# Power.net
KiCad netlist of a schematic drawn in EAGLE
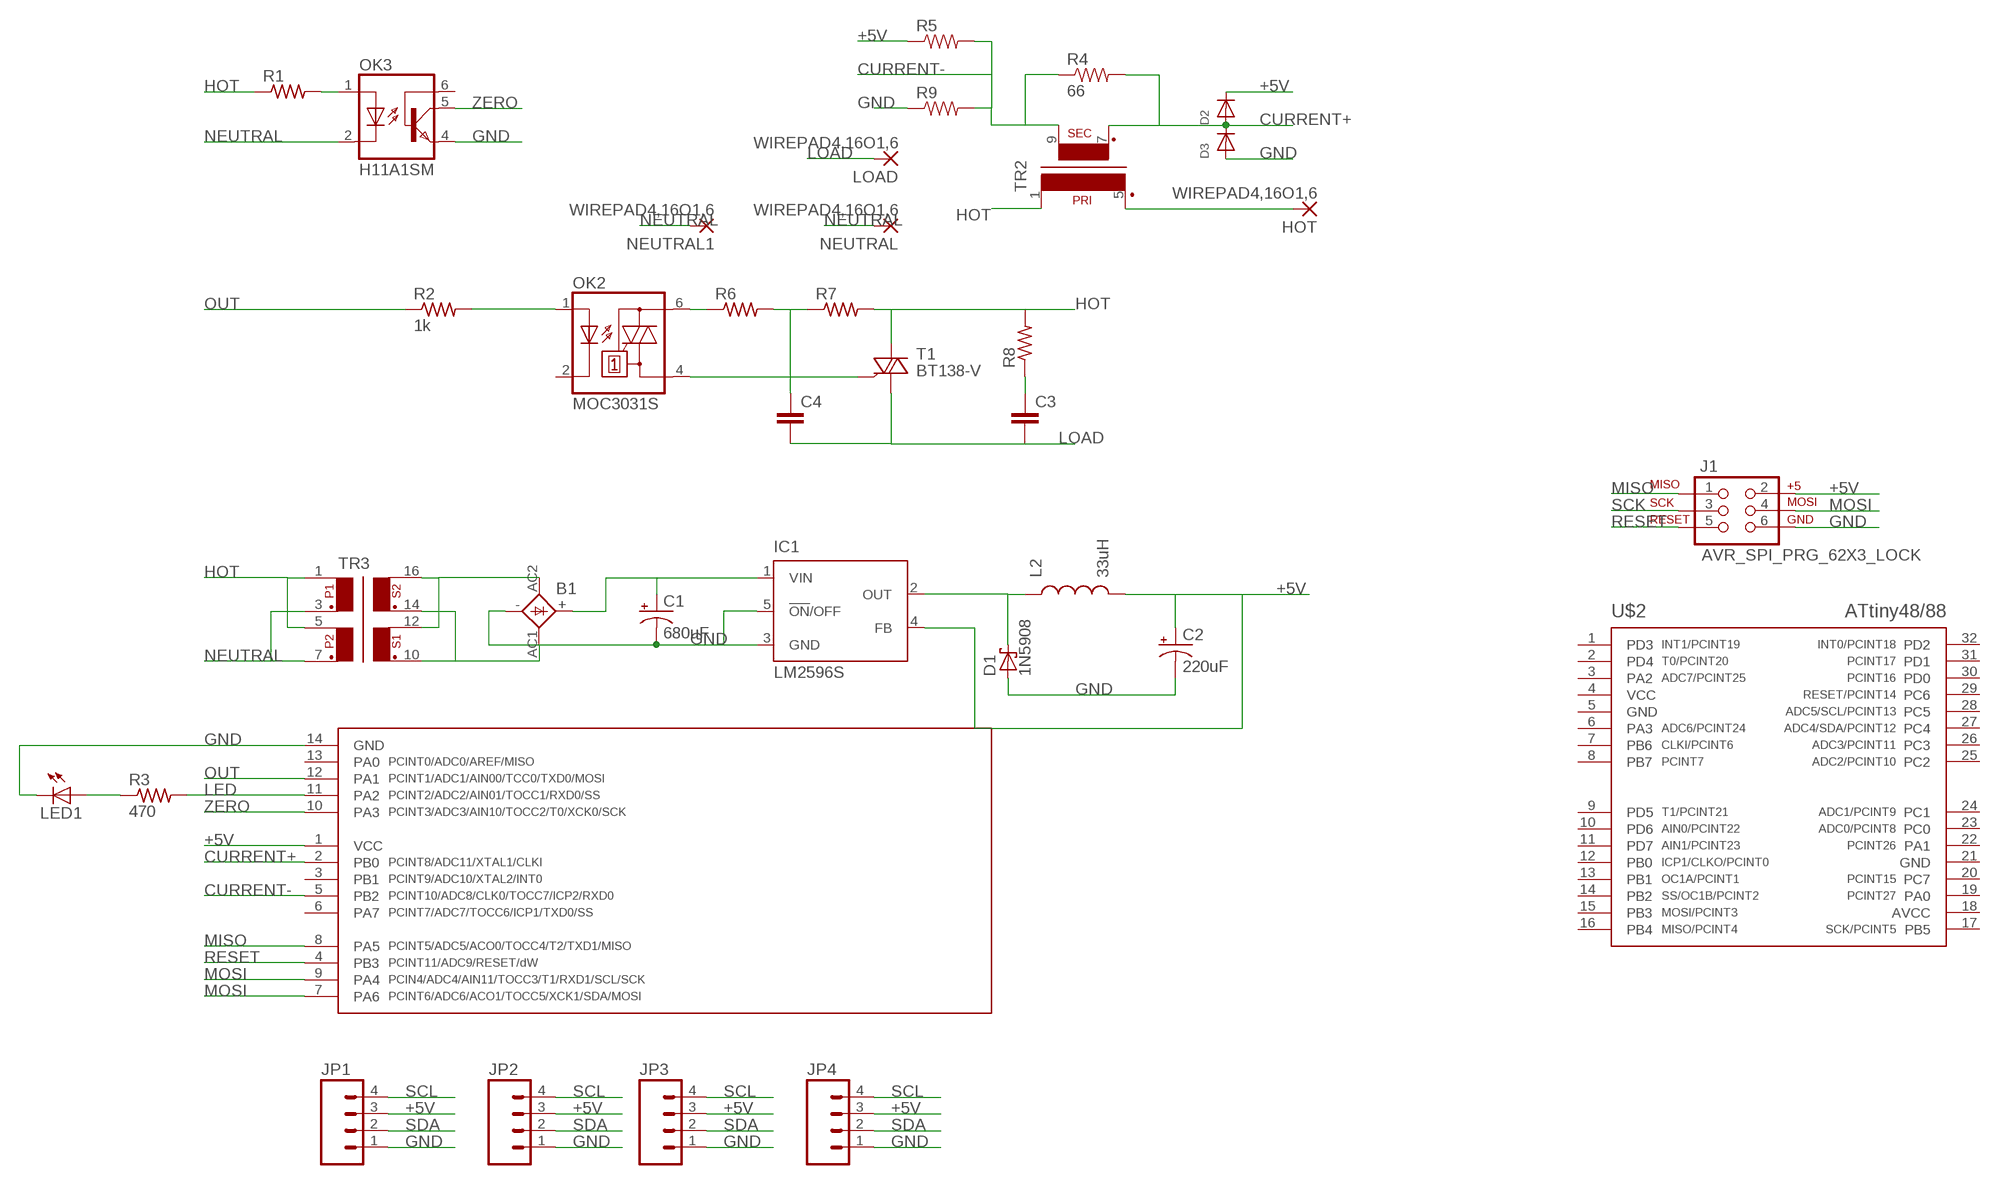
[diagram p0: schematic, sheet 1]

(export (version "E")
  (design (tool "Eeschema 10.0.6"))
  (components
    (comp (ref "B1")
      (value "GBU4")
      (footprint "eagle-import:GBU4S")
      (libsource (lib "eagle-import") (part "GBU4"))
    )
    (comp (ref "C1")
      (value "680uF")
      (footprint "eagle-import:PANASONIC_H13")
      (libsource (lib "eagle-import") (part "CAP_POLH13"))
    )
    (comp (ref "C2")
      (value "220uF")
      (footprint "eagle-import:PANASONIC_D")
      (libsource (lib "eagle-import") (part "CAP_POLD"))
    )
    (comp (ref "C3")
      (value "C-EUC1206")
      (footprint "eagle-import:C1206")
      (libsource (lib "eagle-import") (part "C-EUC1206"))
    )
    (comp (ref "C4")
      (value "C-EUC1206")
      (footprint "eagle-import:C1206")
      (libsource (lib "eagle-import") (part "C-EUC1206"))
    )
    (comp (ref "D1")
      (value "1N5908")
      (footprint "eagle-import:C4111-15")
      (libsource (lib "eagle-import") (part "1N5908"))
    )
    (comp (ref "D2")
      (value "DIODESMA")
      (footprint "eagle-import:SMADIODE")
      (libsource (lib "eagle-import") (part "DIODESMA"))
    )
    (comp (ref "D3")
      (value "DIODESMA")
      (footprint "eagle-import:SMADIODE")
      (libsource (lib "eagle-import") (part "DIODESMA"))
    )
    (comp (ref "HOT")
      (value "WIREPAD4,16O1,6")
      (footprint "eagle-import:4,16O1,6")
      (libsource (lib "eagle-import") (part "WIREPAD4,16O1,6"))
    )
    (comp (ref "IC1")
      (value "LM2596S")
      (footprint "eagle-import:TO263-5")
      (fields (field (name "MF") "NATIONAL SEMICONDUCTOR") (field (name "MPN") "LM2596S-ADJ/NOPB"))
      (libsource (lib "eagle-import") (part "LM2596S"))
    )
    (comp (ref "J1")
      (value "AVR_SPI_PRG_62X3_LOCK")
      (footprint "eagle-import:2X3_LOCK")
      (libsource (lib "eagle-import") (part "AVR_SPI_PRG_62X3_LOCK"))
    )
    (comp (ref "JP1")
      (value "M04JST-PTH")
      (footprint "eagle-import:JST-4-PTH")
      (libsource (lib "eagle-import") (part "M04JST-PTH"))
    )
    (comp (ref "JP2")
      (value "M04JST-PTH")
      (footprint "eagle-import:JST-4-PTH")
      (libsource (lib "eagle-import") (part "M04JST-PTH"))
    )
    (comp (ref "JP3")
      (value "M04JST-PTH")
      (footprint "eagle-import:JST-4-PTH")
      (libsource (lib "eagle-import") (part "M04JST-PTH"))
    )
    (comp (ref "JP4")
      (value "M04JST-PTH")
      (footprint "eagle-import:JST-4-PTH")
      (libsource (lib "eagle-import") (part "M04JST-PTH"))
    )
    (comp (ref "L2")
      (value "33uH")
      (footprint "eagle-import:SRN6045")
      (libsource (lib "eagle-import") (part "INDUCTORBOURNS_SRN6045"))
    )
    (comp (ref "LED1")
      (value "LED1206")
      (footprint "eagle-import:LED-1206")
      (libsource (lib "eagle-import") (part "LED1206"))
    )
    (comp (ref "LOAD")
      (value "WIREPAD4,16O1,6")
      (footprint "eagle-import:4,16O1,6")
      (libsource (lib "eagle-import") (part "WIREPAD4,16O1,6"))
    )
    (comp (ref "NEUTRAL")
      (value "WIREPAD4,16O1,6")
      (footprint "eagle-import:4,16O1,6")
      (libsource (lib "eagle-import") (part "WIREPAD4,16O1,6"))
    )
    (comp (ref "NEUTRAL1")
      (value "WIREPAD4,16O1,6")
      (footprint "eagle-import:4,16O1,6")
      (libsource (lib "eagle-import") (part "WIREPAD4,16O1,6"))
    )
    (comp (ref "OK2")
      (value "MOC3031S")
      (footprint "eagle-import:DIL6-SMD")
      (fields (field (name "MF") "FAIRCHILD SEMICONDUCTOR") (field (name "MPN") "MOC3031SM"))
      (libsource (lib "eagle-import") (part "MOC30S31"))
    )
    (comp (ref "OK3")
      (value "H11A1SM")
      (footprint "eagle-import:DIL6-SMD")
      (libsource (lib "eagle-import") (part "H11A?MS1"))
    )
    (comp (ref "R1")
      (value "R-US_R1206")
      (footprint "eagle-import:R1206")
      (libsource (lib "eagle-import") (part "R-US_R1206"))
    )
    (comp (ref "R2")
      (value "1k")
      (footprint "eagle-import:R1206")
      (libsource (lib "eagle-import") (part "R-US_R1206"))
    )
    (comp (ref "R3")
      (value "470")
      (footprint "eagle-import:R1206")
      (libsource (lib "eagle-import") (part "R-US_R1206"))
    )
    (comp (ref "R4")
      (value "66")
      (footprint "eagle-import:1206")
      (libsource (lib "eagle-import") (part "RESISTOR1206"))
    )
    (comp (ref "R5")
      (value "RESISTOR1206")
      (footprint "eagle-import:1206")
      (libsource (lib "eagle-import") (part "RESISTOR1206"))
    )
    (comp (ref "R6")
      (value "R-US_R1206")
      (footprint "eagle-import:R1206")
      (libsource (lib "eagle-import") (part "R-US_R1206"))
    )
    (comp (ref "R7")
      (value "R-US_R1206")
      (footprint "eagle-import:R1206")
      (libsource (lib "eagle-import") (part "R-US_R1206"))
    )
    (comp (ref "R8")
      (value "R-US_R1206")
      (footprint "eagle-import:R1206")
      (libsource (lib "eagle-import") (part "R-US_R1206"))
    )
    (comp (ref "R9")
      (value "RESISTOR1206")
      (footprint "eagle-import:1206")
      (libsource (lib "eagle-import") (part "RESISTOR1206"))
    )
    (comp (ref "T1")
      (value "BT138-V")
      (footprint "eagle-import:TO220BV")
      (libsource (lib "eagle-import") (part "BT138-V"))
    )
    (comp (ref "TR2")
      (value "VV11")
      (footprint "eagle-import:VV11")
      (libsource (lib "eagle-import") (part "VV11"))
    )
    (comp (ref "TR3")
      (value "FT04-10")
      (footprint "eagle-import:FT04-10")
      (libsource (lib "eagle-import") (part "FT04-10"))
    )
    (comp (ref "U$1")
      (value "TINY841")
      (footprint "eagle-import:SOIC14")
      (libsource (lib "eagle-import") (part "TINY841"))
    )
    (comp (ref "U$2")
      (value "ATTINY48/88-TQFP")
      (footprint "eagle-import:TQFP-32")
      (libsource (lib "eagle-import") (part "ATTINY48/88-TQFP"))
    )
  )
  (nets
    (net (code "1") (name "/+5V") (class "Default")
      (node (ref "C2") (pin "+") (pinfunction "+_+") (pintype "passive"))
      (node (ref "D2") (pin "C") (pinfunction "C_C") (pintype "passive"))
      (node (ref "IC1") (pin "4") (pinfunction "FB_4") (pintype "input"))
      (node (ref "J1") (pin "2") (pinfunction "2_2") (pintype "passive"))
      (node (ref "JP1") (pin "3") (pinfunction "3_3") (pintype "passive"))
      (node (ref "JP2") (pin "3") (pinfunction "3_3") (pintype "passive"))
      (node (ref "JP3") (pin "3") (pinfunction "3_3") (pintype "passive"))
      (node (ref "JP4") (pin "3") (pinfunction "3_3") (pintype "passive"))
      (node (ref "L2") (pin "2") (pinfunction "2_2") (pintype "passive"))
      (node (ref "R5") (pin "1") (pinfunction "1_1") (pintype "passive"))
      (node (ref "U$1") (pin "1") (pinfunction "VCC_1") (pintype "bidirectional"))
    )
    (net (code "2") (name "/AVCC") (class "Default")
      (node (ref "U$2") (pin "18") (pinfunction "AVCC_18") (pintype "power_in"))
    )
    (net (code "3") (name "/CURRENT+") (class "Default")
      (node (ref "D2") (pin "A") (pinfunction "A_A") (pintype "passive"))
      (node (ref "D3") (pin "C") (pinfunction "C_C") (pintype "passive"))
      (node (ref "R4") (pin "2") (pinfunction "2_2") (pintype "passive"))
      (node (ref "TR2") (pin "7") (pinfunction "S3_7") (pintype "passive"))
      (node (ref "U$1") (pin "2") (pinfunction "PB0_2") (pintype "bidirectional"))
    )
    (net (code "4") (name "/CURRENT-") (class "Default")
      (node (ref "R4") (pin "1") (pinfunction "1_1") (pintype "passive"))
      (node (ref "R5") (pin "2") (pinfunction "2_2") (pintype "passive"))
      (node (ref "R9") (pin "2") (pinfunction "2_2") (pintype "passive"))
      (node (ref "TR2") (pin "9") (pinfunction "S4_9") (pintype "passive"))
      (node (ref "U$1") (pin "5") (pinfunction "PB2_5") (pintype "bidirectional"))
    )
    (net (code "5") (name "/GND") (class "Default")
      (node (ref "B1") (pin "-") (pinfunction "-_-") (pintype "passive"))
      (node (ref "C1") (pin "-") (pinfunction "-_-") (pintype "passive"))
      (node (ref "C2") (pin "-") (pinfunction "-_-") (pintype "passive"))
      (node (ref "D1") (pin "A") (pinfunction "A_A") (pintype "passive"))
      (node (ref "D3") (pin "A") (pinfunction "A_A") (pintype "passive"))
      (node (ref "IC1") (pin "3") (pinfunction "GND_3") (pintype "power_in"))
      (node (ref "IC1") (pin "5") (pinfunction "~{ON}/OFF_5") (pintype "input"))
      (node (ref "J1") (pin "6") (pinfunction "6_6") (pintype "passive"))
      (node (ref "JP1") (pin "1") (pinfunction "1_1") (pintype "passive"))
      (node (ref "JP2") (pin "1") (pinfunction "1_1") (pintype "passive"))
      (node (ref "JP3") (pin "1") (pinfunction "1_1") (pintype "passive"))
      (node (ref "JP4") (pin "1") (pinfunction "1_1") (pintype "passive"))
      (node (ref "LED1") (pin "C") (pinfunction "C_C") (pintype "passive"))
      (node (ref "OK3") (pin "4") (pinfunction "EMI_4") (pintype "passive"))
      (node (ref "R9") (pin "1") (pinfunction "1_1") (pintype "passive"))
      (node (ref "U$1") (pin "14") (pinfunction "GND_14") (pintype "bidirectional"))
    )
    (net (code "6") (name "/HOT") (class "Default")
      (node (ref "R1") (pin "1") (pinfunction "1_1") (pintype "passive"))
      (node (ref "R7") (pin "2") (pinfunction "2_2") (pintype "passive"))
      (node (ref "R8") (pin "2") (pinfunction "2_2") (pintype "passive"))
      (node (ref "T1") (pin "T2") (pinfunction "A2_T2") (pintype "passive"))
      (node (ref "TR2") (pin "1") (pinfunction "P1_1") (pintype "passive"))
      (node (ref "TR3") (pin "1") (pinfunction "1_1") (pintype "passive"))
      (node (ref "TR3") (pin "5") (pinfunction "3_5") (pintype "passive"))
    )
    (net (code "7") (name "/LED") (class "Default")
      (node (ref "R3") (pin "2") (pinfunction "2_2") (pintype "passive"))
      (node (ref "U$1") (pin "11") (pinfunction "PA2_11") (pintype "bidirectional"))
    )
    (net (code "8") (name "/LOAD") (class "Default")
      (node (ref "C3") (pin "2") (pinfunction "2_2") (pintype "passive"))
      (node (ref "C4") (pin "2") (pinfunction "2_2") (pintype "passive"))
      (node (ref "LOAD") (pin "1") (pinfunction "P_1") (pintype "passive"))
      (node (ref "T1") (pin "T1") (pinfunction "A1_T1") (pintype "passive"))
    )
    (net (code "9") (name "/MISO") (class "Default")
      (node (ref "J1") (pin "1") (pinfunction "1_1") (pintype "passive"))
      (node (ref "U$1") (pin "8") (pinfunction "PA5_8") (pintype "bidirectional"))
    )
    (net (code "10") (name "/MOSI") (class "Default")
      (node (ref "J1") (pin "4") (pinfunction "4_4") (pintype "passive"))
      (node (ref "U$1") (pin "7") (pinfunction "PA6_7") (pintype "bidirectional"))
      (node (ref "U$1") (pin "9") (pinfunction "PA4_9") (pintype "bidirectional"))
    )
    (net (code "11") (name "/NEUTRAL") (class "Default")
      (node (ref "NEUTRAL") (pin "1") (pinfunction "P_1") (pintype "passive"))
      (node (ref "NEUTRAL1") (pin "1") (pinfunction "P_1") (pintype "passive"))
      (node (ref "OK3") (pin "2") (pinfunction "C_2") (pintype "passive"))
      (node (ref "TR3") (pin "3") (pinfunction "2_3") (pintype "passive"))
      (node (ref "TR3") (pin "7") (pinfunction "4_7") (pintype "passive"))
    )
    (net (code "12") (name "/OUT") (class "Default")
      (node (ref "R2") (pin "1") (pinfunction "1_1") (pintype "passive"))
      (node (ref "U$1") (pin "12") (pinfunction "PA1_12") (pintype "bidirectional"))
    )
    (net (code "13") (name "/RESET") (class "Default")
      (node (ref "J1") (pin "5") (pinfunction "5_5") (pintype "passive"))
      (node (ref "U$1") (pin "4") (pinfunction "PB3_4") (pintype "bidirectional"))
    )
    (net (code "14") (name "/SCK") (class "Default")
      (node (ref "J1") (pin "3") (pinfunction "3_3") (pintype "passive"))
    )
    (net (code "15") (name "/SCL") (class "Default")
      (node (ref "JP1") (pin "4") (pinfunction "4_4") (pintype "passive"))
      (node (ref "JP2") (pin "4") (pinfunction "4_4") (pintype "passive"))
      (node (ref "JP3") (pin "4") (pinfunction "4_4") (pintype "passive"))
      (node (ref "JP4") (pin "4") (pinfunction "4_4") (pintype "passive"))
    )
    (net (code "16") (name "/SDA") (class "Default")
      (node (ref "JP1") (pin "2") (pinfunction "2_2") (pintype "passive"))
      (node (ref "JP2") (pin "2") (pinfunction "2_2") (pintype "passive"))
      (node (ref "JP3") (pin "2") (pinfunction "2_2") (pintype "passive"))
      (node (ref "JP4") (pin "2") (pinfunction "2_2") (pintype "passive"))
    )
    (net (code "17") (name "/ZERO") (class "Default")
      (node (ref "OK3") (pin "5") (pinfunction "COL_5") (pintype "passive"))
      (node (ref "U$1") (pin "10") (pinfunction "PA3_10") (pintype "bidirectional"))
    )
    (net (code "18") (name "Net-(B1-AC1)") (class "Default")
      (node (ref "B1") (pin "AC2") (pinfunction "AC1_AC2") (pintype "passive"))
      (node (ref "TR3") (pin "12") (pinfunction "6_12") (pintype "passive"))
      (node (ref "TR3") (pin "16") (pinfunction "8_16") (pintype "passive"))
    )
    (net (code "19") (name "Net-(B1-AC2)") (class "Default")
      (node (ref "B1") (pin "AC1") (pinfunction "AC2_AC1") (pintype "passive"))
      (node (ref "TR3") (pin "10") (pinfunction "5_10") (pintype "passive"))
      (node (ref "TR3") (pin "14") (pinfunction "7_14") (pintype "passive"))
    )
    (net (code "20") (name "Net-(C3-Pad1)") (class "Default")
      (node (ref "C3") (pin "1") (pinfunction "1_1") (pintype "passive"))
      (node (ref "R8") (pin "1") (pinfunction "1_1") (pintype "passive"))
    )
    (net (code "21") (name "Net-(C4-Pad1)") (class "Default")
      (node (ref "C4") (pin "1") (pinfunction "1_1") (pintype "passive"))
      (node (ref "R6") (pin "2") (pinfunction "2_2") (pintype "passive"))
      (node (ref "R7") (pin "1") (pinfunction "1_1") (pintype "passive"))
    )
    (net (code "22") (name "Net-(HOT-P)") (class "Default")
      (node (ref "HOT") (pin "1") (pinfunction "P_1") (pintype "passive"))
      (node (ref "TR2") (pin "5") (pinfunction "P2_5") (pintype "passive"))
    )
    (net (code "23") (name "Net-(IC1-OUT)") (class "Default")
      (node (ref "D1") (pin "C") (pinfunction "C_C") (pintype "passive"))
      (node (ref "IC1") (pin "2") (pinfunction "OUT_2") (pintype "output"))
      (node (ref "L2") (pin "1") (pinfunction "1_1") (pintype "passive"))
    )
    (net (code "24") (name "Net-(IC1-VIN)") (class "Default")
      (node (ref "B1") (pin "+") (pinfunction "+_+") (pintype "passive"))
      (node (ref "C1") (pin "+") (pinfunction "+_+") (pintype "passive"))
      (node (ref "IC1") (pin "1") (pinfunction "VIN_1") (pintype "input"))
    )
    (net (code "25") (name "Net-(LED1-PadA)") (class "Default")
      (node (ref "LED1") (pin "A") (pinfunction "A_A") (pintype "passive"))
      (node (ref "R3") (pin "1") (pinfunction "1_1") (pintype "passive"))
    )
    (net (code "26") (name "Net-(OK2-A)") (class "Default")
      (node (ref "OK2") (pin "1") (pinfunction "A_1") (pintype "passive"))
      (node (ref "R2") (pin "2") (pinfunction "2_2") (pintype "passive"))
    )
    (net (code "27") (name "Net-(OK2-A1)") (class "Default")
      (node (ref "OK2") (pin "4") (pinfunction "A1_4") (pintype "passive"))
      (node (ref "T1") (pin "G") (pinfunction "G_G") (pintype "passive"))
    )
    (net (code "28") (name "Net-(OK2-A2)") (class "Default")
      (node (ref "OK2") (pin "6") (pinfunction "A2_6") (pintype "passive"))
      (node (ref "R6") (pin "1") (pinfunction "1_1") (pintype "passive"))
    )
    (net (code "29") (name "Net-(OK3-A)") (class "Default")
      (node (ref "OK3") (pin "1") (pinfunction "A_1") (pintype "passive"))
      (node (ref "R1") (pin "2") (pinfunction "2_2") (pintype "passive"))
    )
    (net (code "30") (name "unconnected-(OK2-C-Pad2)") (class "Default")
      (node (ref "OK2") (pin "2") (pinfunction "C_2") (pintype "passive"))
    )
    (net (code "31") (name "unconnected-(OK3-BAS-Pad6)") (class "Default")
      (node (ref "OK3") (pin "6") (pinfunction "BAS_6") (pintype "passive"))
    )
    (net (code "32") (name "unconnected-(U$1-PA0-Pad13)") (class "Default")
      (node (ref "U$1") (pin "13") (pinfunction "PA0_13") (pintype "bidirectional"))
    )
    (net (code "33") (name "unconnected-(U$1-PA7-Pad6)") (class "Default")
      (node (ref "U$1") (pin "6") (pinfunction "PA7_6") (pintype "bidirectional"))
    )
    (net (code "34") (name "unconnected-(U$1-PB1-Pad3)") (class "Default")
      (node (ref "U$1") (pin "3") (pinfunction "PB1_3") (pintype "bidirectional"))
    )
    (net (code "35") (name "unconnected-(U$2-GND-Pad5)") (class "Default")
      (node (ref "U$2") (pin "5") (pinfunction "GND_5") (pintype "bidirectional"))
    )
    (net (code "36") (name "unconnected-(U$2-GND-Pad21)") (class "Default")
      (node (ref "U$2") (pin "21") (pinfunction "GND_21") (pintype "bidirectional"))
    )
    (net (code "37") (name "unconnected-(U$2-PA0-Pad19)") (class "Default")
      (node (ref "U$2") (pin "19") (pinfunction "PA0_19") (pintype "bidirectional"))
    )
    (net (code "38") (name "unconnected-(U$2-PA1-Pad22)") (class "Default")
      (node (ref "U$2") (pin "22") (pinfunction "PA1_22") (pintype "bidirectional"))
    )
    (net (code "39") (name "unconnected-(U$2-PA2-Pad3)") (class "Default")
      (node (ref "U$2") (pin "3") (pinfunction "PA2_3") (pintype "bidirectional"))
    )
    (net (code "40") (name "unconnected-(U$2-PA3-Pad6)") (class "Default")
      (node (ref "U$2") (pin "6") (pinfunction "PA3_6") (pintype "bidirectional"))
    )
    (net (code "41") (name "unconnected-(U$2-PB0-Pad12)") (class "Default")
      (node (ref "U$2") (pin "12") (pinfunction "PB0_12") (pintype "bidirectional"))
    )
    (net (code "42") (name "unconnected-(U$2-PB1-Pad13)") (class "Default")
      (node (ref "U$2") (pin "13") (pinfunction "PB1_13") (pintype "bidirectional"))
    )
    (net (code "43") (name "unconnected-(U$2-PB2-Pad14)") (class "Default")
      (node (ref "U$2") (pin "14") (pinfunction "PB2_14") (pintype "bidirectional"))
    )
    (net (code "44") (name "unconnected-(U$2-PB3-Pad15)") (class "Default")
      (node (ref "U$2") (pin "15") (pinfunction "PB3_15") (pintype "bidirectional"))
    )
    (net (code "45") (name "unconnected-(U$2-PB4-Pad16)") (class "Default")
      (node (ref "U$2") (pin "16") (pinfunction "PB4_16") (pintype "bidirectional"))
    )
    (net (code "46") (name "unconnected-(U$2-PB5-Pad17)") (class "Default")
      (node (ref "U$2") (pin "17") (pinfunction "PB5_17") (pintype "bidirectional"))
    )
    (net (code "47") (name "unconnected-(U$2-PB6-Pad7)") (class "Default")
      (node (ref "U$2") (pin "7") (pinfunction "PB6_7") (pintype "bidirectional"))
    )
    (net (code "48") (name "unconnected-(U$2-PB7-Pad8)") (class "Default")
      (node (ref "U$2") (pin "8") (pinfunction "PB7_8") (pintype "bidirectional"))
    )
    (net (code "49") (name "unconnected-(U$2-PC0-Pad23)") (class "Default")
      (node (ref "U$2") (pin "23") (pinfunction "PC0_23") (pintype "bidirectional"))
    )
    (net (code "50") (name "unconnected-(U$2-PC1-Pad24)") (class "Default")
      (node (ref "U$2") (pin "24") (pinfunction "PC1_24") (pintype "bidirectional"))
    )
    (net (code "51") (name "unconnected-(U$2-PC2-Pad25)") (class "Default")
      (node (ref "U$2") (pin "25") (pinfunction "PC2_25") (pintype "bidirectional"))
    )
    (net (code "52") (name "unconnected-(U$2-PC3-Pad26)") (class "Default")
      (node (ref "U$2") (pin "26") (pinfunction "PC3_26") (pintype "bidirectional"))
    )
    (net (code "53") (name "unconnected-(U$2-PC4-Pad27)") (class "Default")
      (node (ref "U$2") (pin "27") (pinfunction "PC4_27") (pintype "bidirectional"))
    )
    (net (code "54") (name "unconnected-(U$2-PC5-Pad28)") (class "Default")
      (node (ref "U$2") (pin "28") (pinfunction "PC5_28") (pintype "bidirectional"))
    )
    (net (code "55") (name "unconnected-(U$2-PC6-Pad29)") (class "Default")
      (node (ref "U$2") (pin "29") (pinfunction "PC6_29") (pintype "bidirectional"))
    )
    (net (code "56") (name "unconnected-(U$2-PC7-Pad20)") (class "Default")
      (node (ref "U$2") (pin "20") (pinfunction "PC7_20") (pintype "bidirectional"))
    )
    (net (code "57") (name "unconnected-(U$2-PD0-Pad30)") (class "Default")
      (node (ref "U$2") (pin "30") (pinfunction "PD0_30") (pintype "bidirectional"))
    )
    (net (code "58") (name "unconnected-(U$2-PD1-Pad31)") (class "Default")
      (node (ref "U$2") (pin "31") (pinfunction "PD1_31") (pintype "bidirectional"))
    )
    (net (code "59") (name "unconnected-(U$2-PD2-Pad32)") (class "Default")
      (node (ref "U$2") (pin "32") (pinfunction "PD2_32") (pintype "bidirectional"))
    )
    (net (code "60") (name "unconnected-(U$2-PD3-Pad1)") (class "Default")
      (node (ref "U$2") (pin "1") (pinfunction "PD3_1") (pintype "bidirectional"))
    )
    (net (code "61") (name "unconnected-(U$2-PD4-Pad2)") (class "Default")
      (node (ref "U$2") (pin "2") (pinfunction "PD4_2") (pintype "bidirectional"))
    )
    (net (code "62") (name "unconnected-(U$2-PD5-Pad9)") (class "Default")
      (node (ref "U$2") (pin "9") (pinfunction "PD5_9") (pintype "bidirectional"))
    )
    (net (code "63") (name "unconnected-(U$2-PD6-Pad10)") (class "Default")
      (node (ref "U$2") (pin "10") (pinfunction "PD6_10") (pintype "bidirectional"))
    )
    (net (code "64") (name "unconnected-(U$2-PD7-Pad11)") (class "Default")
      (node (ref "U$2") (pin "11") (pinfunction "PD7_11") (pintype "bidirectional"))
    )
    (net (code "65") (name "unconnected-(U$2-VCC-Pad4)") (class "Default")
      (node (ref "U$2") (pin "4") (pinfunction "VCC_4") (pintype "bidirectional"))
    )
  )
)
